# modem-v1-rev1.net
KiCad netlist of a schematic drawn in EAGLE
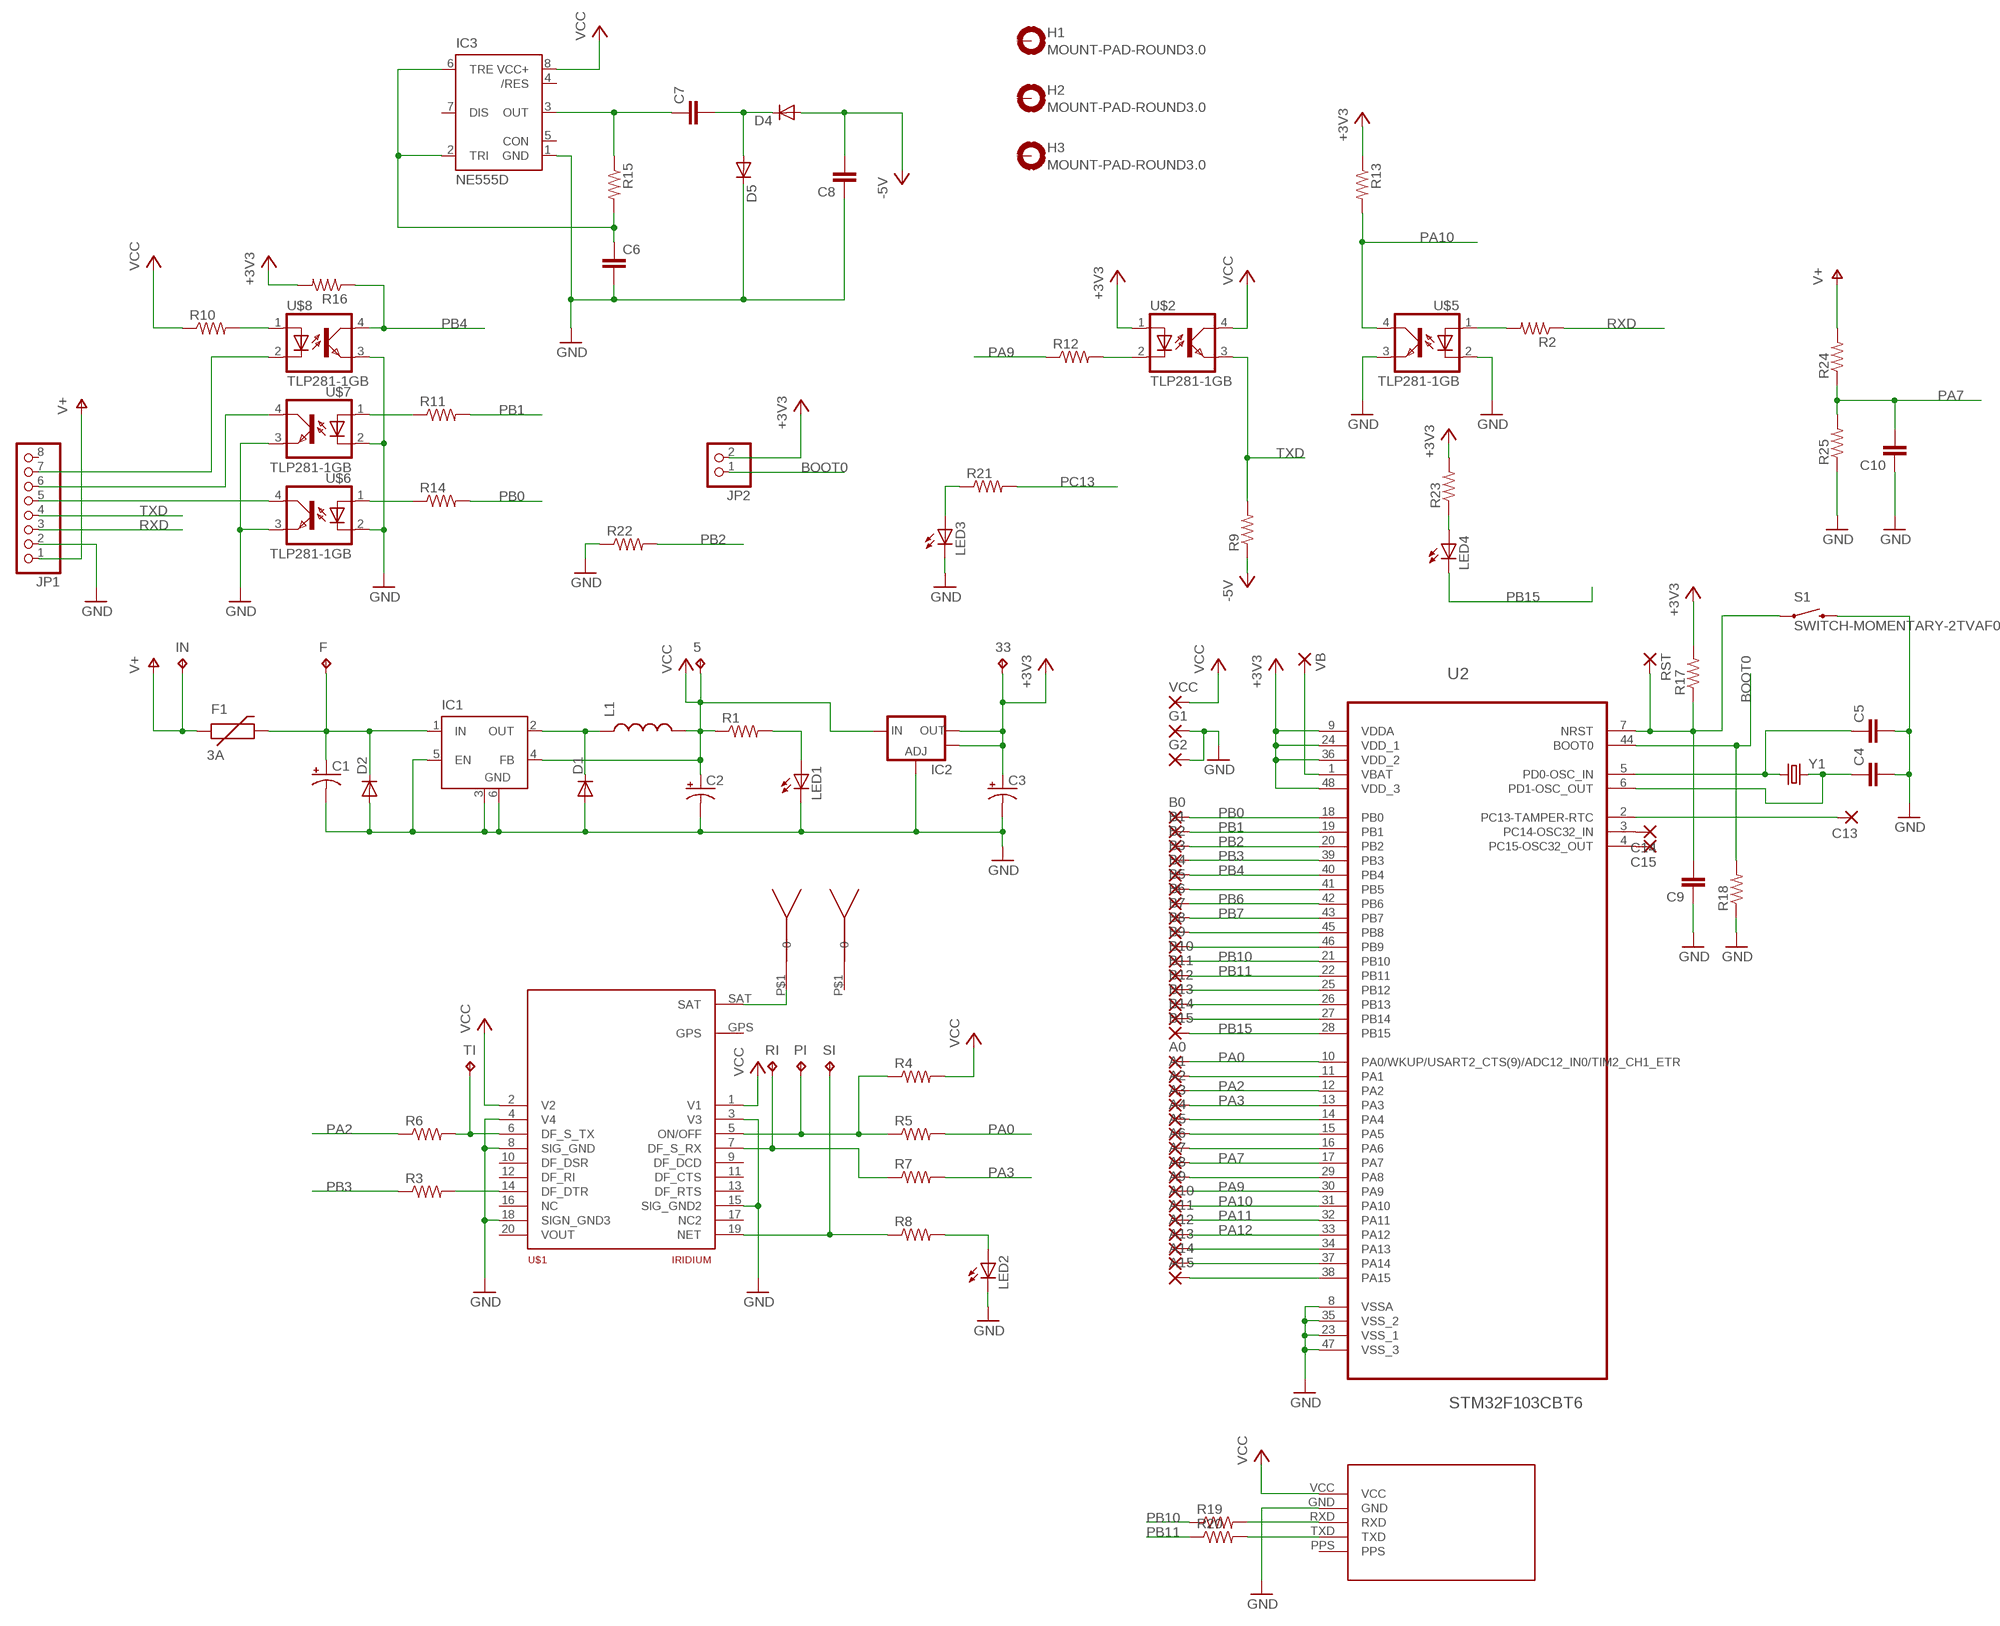
[diagram p0: schematic, sheet 1]

(export (version "E")
  (design (tool "Eeschema 10.0.6"))
  (components
    (comp (ref "5")
      (value "TPTP15R")
      (footprint "eagle-import:TP15R")
      (libsource (lib "eagle-import") (part "TPTP15R"))
    )
    (comp (ref "33")
      (value "TP1")
      (footprint "eagle-import:TP15R")
      (libsource (lib "eagle-import") (part "TPTP15R"))
    )
    (comp (ref "A0")
      (value "1,6/0,8")
      (footprint "eagle-import:1,6_0,8")
      (libsource (lib "eagle-import") (part "1,6/0,8"))
    )
    (comp (ref "A1")
      (value "1,6/0,8")
      (footprint "eagle-import:1,6_0,8")
      (libsource (lib "eagle-import") (part "1,6/0,8"))
    )
    (comp (ref "A2")
      (value "1,6/0,8")
      (footprint "eagle-import:1,6_0,8")
      (libsource (lib "eagle-import") (part "1,6/0,8"))
    )
    (comp (ref "A3")
      (value "1,6/0,8")
      (footprint "eagle-import:1,6_0,8")
      (libsource (lib "eagle-import") (part "1,6/0,8"))
    )
    (comp (ref "A4")
      (value "1,6/0,8")
      (footprint "eagle-import:1,6_0,8")
      (libsource (lib "eagle-import") (part "1,6/0,8"))
    )
    (comp (ref "A5")
      (value "1,6/0,8")
      (footprint "eagle-import:1,6_0,8")
      (libsource (lib "eagle-import") (part "1,6/0,8"))
    )
    (comp (ref "A6")
      (value "1,6/0,8")
      (footprint "eagle-import:1,6_0,8")
      (libsource (lib "eagle-import") (part "1,6/0,8"))
    )
    (comp (ref "A7")
      (value "1,6/0,8")
      (footprint "eagle-import:1,6_0,8")
      (libsource (lib "eagle-import") (part "1,6/0,8"))
    )
    (comp (ref "A8")
      (value "1,6/0,8")
      (footprint "eagle-import:1,6_0,8")
      (libsource (lib "eagle-import") (part "1,6/0,8"))
    )
    (comp (ref "A9")
      (value "1,6/0,8")
      (footprint "eagle-import:1,6_0,8")
      (libsource (lib "eagle-import") (part "1,6/0,8"))
    )
    (comp (ref "A10")
      (value "1,6/0,8")
      (footprint "eagle-import:1,6_0,8")
      (libsource (lib "eagle-import") (part "1,6/0,8"))
    )
    (comp (ref "A11")
      (value "1,6/0,8")
      (footprint "eagle-import:1,6_0,8")
      (libsource (lib "eagle-import") (part "1,6/0,8"))
    )
    (comp (ref "A12")
      (value "1,6/0,8")
      (footprint "eagle-import:1,6_0,8")
      (libsource (lib "eagle-import") (part "1,6/0,8"))
    )
    (comp (ref "A13")
      (value "1,6/0,8")
      (footprint "eagle-import:1,6_0,8")
      (libsource (lib "eagle-import") (part "1,6/0,8"))
    )
    (comp (ref "A14")
      (value "1,6/0,8")
      (footprint "eagle-import:1,6_0,8")
      (libsource (lib "eagle-import") (part "1,6/0,8"))
    )
    (comp (ref "A15")
      (value "1,6/0,8")
      (footprint "eagle-import:1,6_0,8")
      (libsource (lib "eagle-import") (part "1,6/0,8"))
    )
    (comp (ref "B0")
      (value "1,6/0,8")
      (footprint "eagle-import:1,6_0,8")
      (libsource (lib "eagle-import") (part "1,6/0,8"))
    )
    (comp (ref "B1")
      (value "1,6/0,8")
      (footprint "eagle-import:1,6_0,8")
      (libsource (lib "eagle-import") (part "1,6/0,8"))
    )
    (comp (ref "B2")
      (value "1,6/0,8")
      (footprint "eagle-import:1,6_0,8")
      (libsource (lib "eagle-import") (part "1,6/0,8"))
    )
    (comp (ref "B3")
      (value "1,6/0,8")
      (footprint "eagle-import:1,6_0,8")
      (libsource (lib "eagle-import") (part "1,6/0,8"))
    )
    (comp (ref "B4")
      (value "1,6/0,8")
      (footprint "eagle-import:1,6_0,8")
      (libsource (lib "eagle-import") (part "1,6/0,8"))
    )
    (comp (ref "B5")
      (value "1,6/0,8")
      (footprint "eagle-import:1,6_0,8")
      (libsource (lib "eagle-import") (part "1,6/0,8"))
    )
    (comp (ref "B6")
      (value "1,6/0,8")
      (footprint "eagle-import:1,6_0,8")
      (libsource (lib "eagle-import") (part "1,6/0,8"))
    )
    (comp (ref "B7")
      (value "1,6/0,8")
      (footprint "eagle-import:1,6_0,8")
      (libsource (lib "eagle-import") (part "1,6/0,8"))
    )
    (comp (ref "B8")
      (value "1,6/0,8")
      (footprint "eagle-import:1,6_0,8")
      (libsource (lib "eagle-import") (part "1,6/0,8"))
    )
    (comp (ref "B9")
      (value "1,6/0,8")
      (footprint "eagle-import:1,6_0,8")
      (libsource (lib "eagle-import") (part "1,6/0,8"))
    )
    (comp (ref "B10")
      (value "1,6/0,8")
      (footprint "eagle-import:1,6_0,8")
      (libsource (lib "eagle-import") (part "1,6/0,8"))
    )
    (comp (ref "B11")
      (value "1,6/0,8")
      (footprint "eagle-import:1,6_0,8")
      (libsource (lib "eagle-import") (part "1,6/0,8"))
    )
    (comp (ref "B12")
      (value "1,6/0,8")
      (footprint "eagle-import:1,6_0,8")
      (libsource (lib "eagle-import") (part "1,6/0,8"))
    )
    (comp (ref "B13")
      (value "1,6/0,8")
      (footprint "eagle-import:1,6_0,8")
      (libsource (lib "eagle-import") (part "1,6/0,8"))
    )
    (comp (ref "B14")
      (value "1,6/0,8")
      (footprint "eagle-import:1,6_0,8")
      (libsource (lib "eagle-import") (part "1,6/0,8"))
    )
    (comp (ref "B15")
      (value "1,6/0,8")
      (footprint "eagle-import:1,6_0,8")
      (libsource (lib "eagle-import") (part "1,6/0,8"))
    )
    (comp (ref "C1")
      (value "CAP_POLG")
      (footprint "eagle-import:PANASONIC_G")
      (libsource (lib "eagle-import") (part "CAP_POLG"))
    )
    (comp (ref "C2")
      (value "CAP_POLD")
      (footprint "eagle-import:PANASONIC_D")
      (libsource (lib "eagle-import") (part "CAP_POLD"))
    )
    (comp (ref "C3")
      (value "CAP_POLD")
      (footprint "eagle-import:PANASONIC_D")
      (libsource (lib "eagle-import") (part "CAP_POLD"))
    )
    (comp (ref "C4")
      (value "CAP0805")
      (footprint "eagle-import:0805")
      (libsource (lib "eagle-import") (part "CAP0805"))
    )
    (comp (ref "C5")
      (value "CAP0805")
      (footprint "eagle-import:0805")
      (libsource (lib "eagle-import") (part "CAP0805"))
    )
    (comp (ref "C6")
      (value "CAP0805")
      (footprint "eagle-import:0805")
      (libsource (lib "eagle-import") (part "CAP0805"))
    )
    (comp (ref "C7")
      (value "CAP0805")
      (footprint "eagle-import:0805")
      (libsource (lib "eagle-import") (part "CAP0805"))
    )
    (comp (ref "C8")
      (value "CAP0805")
      (footprint "eagle-import:0805")
      (libsource (lib "eagle-import") (part "CAP0805"))
    )
    (comp (ref "C9")
      (value "CAP0805")
      (footprint "eagle-import:0805")
      (libsource (lib "eagle-import") (part "CAP0805"))
    )
    (comp (ref "C10")
      (value "CAP0805")
      (footprint "eagle-import:0805")
      (libsource (lib "eagle-import") (part "CAP0805"))
    )
    (comp (ref "C13")
      (value "1,6/0,8")
      (footprint "eagle-import:1,6_0,8")
      (libsource (lib "eagle-import") (part "1,6/0,8"))
    )
    (comp (ref "C14")
      (value "1,6/0,8")
      (footprint "eagle-import:1,6_0,8")
      (libsource (lib "eagle-import") (part "1,6/0,8"))
    )
    (comp (ref "C15")
      (value "1,6/0,8")
      (footprint "eagle-import:1,6_0,8")
      (libsource (lib "eagle-import") (part "1,6/0,8"))
    )
    (comp (ref "D1")
      (value "DIODESMA-KIT")
      (footprint "eagle-import:SMA-DIODE-KIT")
      (libsource (lib "eagle-import") (part "DIODESMA-KIT"))
    )
    (comp (ref "D2")
      (value "DIODESMB")
      (footprint "eagle-import:SMB-DIODE")
      (libsource (lib "eagle-import") (part "DIODESMB"))
    )
    (comp (ref "D4")
      (value "DIODESOD")
      (footprint "eagle-import:SOD-323")
      (libsource (lib "eagle-import") (part "DIODESOD"))
    )
    (comp (ref "D5")
      (value "DIODESOD")
      (footprint "eagle-import:SOD-323")
      (libsource (lib "eagle-import") (part "DIODESOD"))
    )
    (comp (ref "F")
      (value "TPTP15R")
      (footprint "eagle-import:TP15R")
      (libsource (lib "eagle-import") (part "TPTP15R"))
    )
    (comp (ref "F1")
      (value "3A")
      (footprint "eagle-import:PTC")
      (libsource (lib "eagle-import") (part "PTCPTH"))
    )
    (comp (ref "G1")
      (value "1,6/0,8")
      (footprint "eagle-import:1,6_0,8")
      (libsource (lib "eagle-import") (part "1,6/0,8"))
    )
    (comp (ref "G2")
      (value "1,6/0,8")
      (footprint "eagle-import:1,6_0,8")
      (libsource (lib "eagle-import") (part "1,6/0,8"))
    )
    (comp (ref "H1")
      (value "MOUNT-PAD-ROUND3.0")
      (footprint "eagle-import:3,0-PAD")
      (libsource (lib "eagle-import") (part "MOUNT-PAD-ROUND3.0"))
    )
    (comp (ref "H2")
      (value "MOUNT-PAD-ROUND3.0")
      (footprint "eagle-import:3,0-PAD")
      (libsource (lib "eagle-import") (part "MOUNT-PAD-ROUND3.0"))
    )
    (comp (ref "H3")
      (value "MOUNT-PAD-ROUND3.0")
      (footprint "eagle-import:3,0-PAD")
      (libsource (lib "eagle-import") (part "MOUNT-PAD-ROUND3.0"))
    )
    (comp (ref "IC1")
      (value "LM2596S")
      (footprint "eagle-import:TO263-5")
      (libsource (lib "eagle-import") (part "LM2596S"))
    )
    (comp (ref "IC2")
      (value "V_REG_LM1117SOT223")
      (footprint "eagle-import:SOT223")
      (libsource (lib "eagle-import") (part "V_REG_LM1117SOT223"))
    )
    (comp (ref "IC3")
      (value "NE555D")
      (footprint "eagle-import:SO08")
      (libsource (lib "eagle-import") (part "NE555D"))
    )
    (comp (ref "IN")
      (value "IN")
      (footprint "eagle-import:TP15R")
      (libsource (lib "eagle-import") (part "TPTP15R"))
    )
    (comp (ref "JP1")
      (value "PINHD-1X8")
      (footprint "eagle-import:1X08")
      (libsource (lib "eagle-import") (part "PINHD-1X8"))
    )
    (comp (ref "JP2")
      (value "PINHD-1X2")
      (footprint "eagle-import:1X02")
      (libsource (lib "eagle-import") (part "PINHD-1X2"))
    )
    (comp (ref "L1")
      (value "INDUCTORPWR")
      (footprint "eagle-import:CDRH125")
      (libsource (lib "eagle-import") (part "INDUCTORPWR"))
    )
    (comp (ref "LED1")
      (value "LED-FKIT-1206")
      (footprint "eagle-import:FKIT-LED-1206")
      (libsource (lib "eagle-import") (part "LED-FKIT-1206"))
    )
    (comp (ref "LED2")
      (value "LED-FKIT-1206")
      (footprint "eagle-import:FKIT-LED-1206")
      (libsource (lib "eagle-import") (part "LED-FKIT-1206"))
    )
    (comp (ref "LED3")
      (value "LED-FKIT-1206")
      (footprint "eagle-import:FKIT-LED-1206")
      (libsource (lib "eagle-import") (part "LED-FKIT-1206"))
    )
    (comp (ref "LED4")
      (value "LED-FKIT-1206")
      (footprint "eagle-import:FKIT-LED-1206")
      (libsource (lib "eagle-import") (part "LED-FKIT-1206"))
    )
    (comp (ref "PI")
      (value "TPTP15R")
      (footprint "eagle-import:TP15R")
      (libsource (lib "eagle-import") (part "TPTP15R"))
    )
    (comp (ref "R1")
      (value "RESISTOR0805-RES")
      (footprint "eagle-import:0805")
      (libsource (lib "eagle-import") (part "RESISTOR0805-RES"))
    )
    (comp (ref "R2")
      (value "RESISTOR0805-RES")
      (footprint "eagle-import:0805")
      (libsource (lib "eagle-import") (part "RESISTOR0805-RES"))
    )
    (comp (ref "R3")
      (value "RESISTOR0805-RES")
      (footprint "eagle-import:0805")
      (libsource (lib "eagle-import") (part "RESISTOR0805-RES"))
    )
    (comp (ref "R4")
      (value "RESISTOR0805-RES")
      (footprint "eagle-import:0805")
      (libsource (lib "eagle-import") (part "RESISTOR0805-RES"))
    )
    (comp (ref "R5")
      (value "RESISTOR0805-RES")
      (footprint "eagle-import:0805")
      (libsource (lib "eagle-import") (part "RESISTOR0805-RES"))
    )
    (comp (ref "R6")
      (value "RESISTOR0805-RES")
      (footprint "eagle-import:0805")
      (libsource (lib "eagle-import") (part "RESISTOR0805-RES"))
    )
    (comp (ref "R7")
      (value "RESISTOR0805-RES")
      (footprint "eagle-import:0805")
      (libsource (lib "eagle-import") (part "RESISTOR0805-RES"))
    )
    (comp (ref "R8")
      (value "RESISTOR0805-RES")
      (footprint "eagle-import:0805")
      (libsource (lib "eagle-import") (part "RESISTOR0805-RES"))
    )
    (comp (ref "R9")
      (value "RESISTOR0805-RES")
      (footprint "eagle-import:0805")
      (libsource (lib "eagle-import") (part "RESISTOR0805-RES"))
    )
    (comp (ref "R10")
      (value "RESISTOR0805-RES")
      (footprint "eagle-import:0805")
      (libsource (lib "eagle-import") (part "RESISTOR0805-RES"))
    )
    (comp (ref "R11")
      (value "RESISTOR0805-RES")
      (footprint "eagle-import:0805")
      (libsource (lib "eagle-import") (part "RESISTOR0805-RES"))
    )
    (comp (ref "R12")
      (value "RESISTOR0805-RES")
      (footprint "eagle-import:0805")
      (libsource (lib "eagle-import") (part "RESISTOR0805-RES"))
    )
    (comp (ref "R13")
      (value "RESISTOR0805-RES")
      (footprint "eagle-import:0805")
      (libsource (lib "eagle-import") (part "RESISTOR0805-RES"))
    )
    (comp (ref "R14")
      (value "RESISTOR0805-RES")
      (footprint "eagle-import:0805")
      (libsource (lib "eagle-import") (part "RESISTOR0805-RES"))
    )
    (comp (ref "R15")
      (value "RESISTOR0805-RES")
      (footprint "eagle-import:0805")
      (libsource (lib "eagle-import") (part "RESISTOR0805-RES"))
    )
    (comp (ref "R16")
      (value "RESISTOR0805-RES")
      (footprint "eagle-import:0805")
      (libsource (lib "eagle-import") (part "RESISTOR0805-RES"))
    )
    (comp (ref "R17")
      (value "RESISTOR0805-RES")
      (footprint "eagle-import:0805")
      (libsource (lib "eagle-import") (part "RESISTOR0805-RES"))
    )
    (comp (ref "R18")
      (value "RESISTOR0805-RES")
      (footprint "eagle-import:0805")
      (libsource (lib "eagle-import") (part "RESISTOR0805-RES"))
    )
    (comp (ref "R19")
      (value "RESISTOR0805-RES")
      (footprint "eagle-import:0805")
      (libsource (lib "eagle-import") (part "RESISTOR0805-RES"))
    )
    (comp (ref "R20")
      (value "RESISTOR0805-RES")
      (footprint "eagle-import:0805")
      (libsource (lib "eagle-import") (part "RESISTOR0805-RES"))
    )
    (comp (ref "R21")
      (value "RESISTOR0805-RES")
      (footprint "eagle-import:0805")
      (libsource (lib "eagle-import") (part "RESISTOR0805-RES"))
    )
    (comp (ref "R22")
      (value "RESISTOR0805-RES")
      (footprint "eagle-import:0805")
      (libsource (lib "eagle-import") (part "RESISTOR0805-RES"))
    )
    (comp (ref "R23")
      (value "RESISTOR0805-RES")
      (footprint "eagle-import:0805")
      (libsource (lib "eagle-import") (part "RESISTOR0805-RES"))
    )
    (comp (ref "R24")
      (value "RESISTOR0805-RES")
      (footprint "eagle-import:0805")
      (libsource (lib "eagle-import") (part "RESISTOR0805-RES"))
    )
    (comp (ref "R25")
      (value "RESISTOR0805-RES")
      (footprint "eagle-import:0805")
      (libsource (lib "eagle-import") (part "RESISTOR0805-RES"))
    )
    (comp (ref "RI")
      (value "TPTP15R")
      (footprint "eagle-import:TP15R")
      (libsource (lib "eagle-import") (part "TPTP15R"))
    )
    (comp (ref "RST")
      (value "1,6/0,8")
      (footprint "eagle-import:1,6_0,8")
      (libsource (lib "eagle-import") (part "1,6/0,8"))
    )
    (comp (ref "S1")
      (value "SWITCH-MOMENTARY-2TVAF02")
      (footprint "eagle-import:TVAF02")
      (libsource (lib "eagle-import") (part "SWITCH-MOMENTARY-2TVAF02"))
    )
    (comp (ref "SI")
      (value "TPTP15R")
      (footprint "eagle-import:TP15R")
      (libsource (lib "eagle-import") (part "TPTP15R"))
    )
    (comp (ref "TI")
      (value "TPTP15R")
      (footprint "eagle-import:TP15R")
      (libsource (lib "eagle-import") (part "TPTP15R"))
    )
    (comp (ref "U$1")
      (value "IRIDIUM-9602")
      (footprint "eagle-import:IRIDIUM-9602")
      (libsource (lib "eagle-import") (part "IRIDIUM-9602"))
    )
    (comp (ref "U$2")
      (value "TLP281-1GB")
      (footprint "eagle-import:TLP281")
      (libsource (lib "eagle-import") (part "TLP281-1GB"))
    )
    (comp (ref "U$3")
      (value "TAOGLASS-ANTENNA")
      (footprint "eagle-import:TAOGLASS-1")
      (libsource (lib "eagle-import") (part "TAOGLASS-ANTENNA"))
    )
    (comp (ref "U$4")
      (value "TAOGLASS-ANTENNA")
      (footprint "eagle-import:TAOGLASS-1")
      (libsource (lib "eagle-import") (part "TAOGLASS-ANTENNA"))
    )
    (comp (ref "U$5")
      (value "TLP281-1GB")
      (footprint "eagle-import:TLP281")
      (libsource (lib "eagle-import") (part "TLP281-1GB"))
    )
    (comp (ref "U$6")
      (value "TLP281-1GB")
      (footprint "eagle-import:TLP281")
      (libsource (lib "eagle-import") (part "TLP281-1GB"))
    )
    (comp (ref "U$7")
      (value "TLP281-1GB")
      (footprint "eagle-import:TLP281")
      (libsource (lib "eagle-import") (part "TLP281-1GB"))
    )
    (comp (ref "U$8")
      (value "TLP281-1GB")
      (footprint "eagle-import:TLP281")
      (libsource (lib "eagle-import") (part "TLP281-1GB"))
    )
    (comp (ref "U1")
      (value "UBLOX_NEO_6M")
      (footprint "eagle-import:NEO-6M")
      (libsource (lib "eagle-import") (part "UBLOX_NEO_6M"))
    )
    (comp (ref "U2")
      (value "STM32F103CBT6")
      (footprint "eagle-import:QFP50P900X900X160-48N")
      (libsource (lib "eagle-import") (part "STM32F103CBT6"))
    )
    (comp (ref "VB")
      (value "1,6/0,8")
      (footprint "eagle-import:1,6_0,8")
      (libsource (lib "eagle-import") (part "1,6/0,8"))
    )
    (comp (ref "VCC")
      (value "1,6/0,8")
      (footprint "eagle-import:1,6_0,8")
      (libsource (lib "eagle-import") (part "1,6/0,8"))
    )
    (comp (ref "Y1")
      (value "CRYSTAL10.5X4.8")
      (footprint "eagle-import:CRYSTAL-SMD-10.5X4.8-2PIN")
      (libsource (lib "eagle-import") (part "CRYSTAL10.5X4.8"))
    )
  )
  (nets
    (net (code "1") (name "+3V3") (class "Default")
      (node (ref "33") (pin "TP") (pinfunction "TP_TP") (pintype "input"))
      (node (ref "C3") (pin "+") (pinfunction "+_+") (pintype "passive"))
      (node (ref "IC2") (pin "2") (pinfunction "OUT_2") (pintype "output"))
      (node (ref "IC2") (pin "4") (pinfunction "OUT_4") (pintype "output"))
      (node (ref "JP2") (pin "2") (pinfunction "2_2") (pintype "passive"))
      (node (ref "R13") (pin "1") (pinfunction "1_1") (pintype "passive"))
      (node (ref "R16") (pin "2") (pinfunction "2_2") (pintype "passive"))
      (node (ref "R17") (pin "2") (pinfunction "2_2") (pintype "passive"))
      (node (ref "R23") (pin "2") (pinfunction "2_2") (pintype "passive"))
      (node (ref "U$2") (pin "1") (pinfunction "A_1") (pintype "passive"))
      (node (ref "U2") (pin "24") (pinfunction "VDD_1_24") (pintype "bidirectional"))
      (node (ref "U2") (pin "36") (pinfunction "VDD_2_36") (pintype "power_in"))
      (node (ref "U2") (pin "48") (pinfunction "VDD_3_48") (pintype "power_in"))
      (node (ref "U2") (pin "9") (pinfunction "VDDA_9") (pintype "power_in"))
    )
    (net (code "2") (name "-5V") (class "Default")
      (node (ref "C8") (pin "2") (pinfunction "2_2") (pintype "passive"))
      (node (ref "D4") (pin "2") (pinfunction "A_2") (pintype "passive"))
      (node (ref "R9") (pin "1") (pinfunction "1_1") (pintype "passive"))
    )
    (net (code "3") (name "/BOOT0") (class "Default")
      (node (ref "JP2") (pin "1") (pinfunction "1_1") (pintype "passive"))
      (node (ref "R18") (pin "2") (pinfunction "2_2") (pintype "passive"))
      (node (ref "U2") (pin "44") (pinfunction "BOOT0_44") (pintype "bidirectional"))
    )
    (net (code "4") (name "/PA0") (class "Default")
      (node (ref "A0") (pin "1") (pinfunction "P_1") (pintype "passive"))
      (node (ref "R5") (pin "2") (pinfunction "2_2") (pintype "passive"))
      (node (ref "U2") (pin "10") (pinfunction "PA0/WKUP/USART2_CTS(9)/ADC12_IN0/TIM2_CH1_ETR_10") (pintype "bidirectional"))
    )
    (net (code "5") (name "/PA2") (class "Default")
      (node (ref "A2") (pin "1") (pinfunction "P_1") (pintype "passive"))
      (node (ref "R6") (pin "1") (pinfunction "1_1") (pintype "passive"))
      (node (ref "U2") (pin "12") (pinfunction "PA2_12") (pintype "bidirectional"))
    )
    (net (code "6") (name "/PA3") (class "Default")
      (node (ref "A3") (pin "1") (pinfunction "P_1") (pintype "passive"))
      (node (ref "R7") (pin "2") (pinfunction "2_2") (pintype "passive"))
      (node (ref "U2") (pin "13") (pinfunction "PA3_13") (pintype "bidirectional"))
    )
    (net (code "7") (name "/PA7") (class "Default")
      (node (ref "A7") (pin "1") (pinfunction "P_1") (pintype "passive"))
      (node (ref "C10") (pin "2") (pinfunction "2_2") (pintype "passive"))
      (node (ref "R24") (pin "1") (pinfunction "1_1") (pintype "passive"))
      (node (ref "R25") (pin "2") (pinfunction "2_2") (pintype "passive"))
      (node (ref "U2") (pin "17") (pinfunction "PA7_17") (pintype "bidirectional"))
    )
    (net (code "8") (name "/PA9") (class "Default")
      (node (ref "A9") (pin "1") (pinfunction "P_1") (pintype "passive"))
      (node (ref "R12") (pin "1") (pinfunction "1_1") (pintype "passive"))
      (node (ref "U2") (pin "30") (pinfunction "PA9_30") (pintype "bidirectional"))
    )
    (net (code "9") (name "/PA10") (class "Default")
      (node (ref "A10") (pin "1") (pinfunction "P_1") (pintype "passive"))
      (node (ref "R13") (pin "2") (pinfunction "2_2") (pintype "passive"))
      (node (ref "U$5") (pin "4") (pinfunction "COL_4") (pintype "passive"))
      (node (ref "U2") (pin "31") (pinfunction "PA10_31") (pintype "bidirectional"))
    )
    (net (code "10") (name "/PA11") (class "Default")
      (node (ref "A11") (pin "1") (pinfunction "P_1") (pintype "passive"))
      (node (ref "U2") (pin "32") (pinfunction "PA11_32") (pintype "power_in"))
    )
    (net (code "11") (name "/PA12") (class "Default")
      (node (ref "A12") (pin "1") (pinfunction "P_1") (pintype "passive"))
      (node (ref "U2") (pin "33") (pinfunction "PA12_33") (pintype "bidirectional"))
    )
    (net (code "12") (name "/PB0") (class "Default")
      (node (ref "B0") (pin "1") (pinfunction "P_1") (pintype "passive"))
      (node (ref "R14") (pin "2") (pinfunction "2_2") (pintype "passive"))
      (node (ref "U2") (pin "18") (pinfunction "PB0_18") (pintype "bidirectional"))
    )
    (net (code "13") (name "/PB1") (class "Default")
      (node (ref "B1") (pin "1") (pinfunction "P_1") (pintype "passive"))
      (node (ref "R11") (pin "2") (pinfunction "2_2") (pintype "passive"))
      (node (ref "U2") (pin "19") (pinfunction "PB1_19") (pintype "bidirectional"))
    )
    (net (code "14") (name "/PB2") (class "Default")
      (node (ref "B2") (pin "1") (pinfunction "P_1") (pintype "passive"))
      (node (ref "R22") (pin "2") (pinfunction "2_2") (pintype "passive"))
      (node (ref "U2") (pin "20") (pinfunction "PB2_20") (pintype "bidirectional"))
    )
    (net (code "15") (name "/PB3") (class "Default")
      (node (ref "B3") (pin "1") (pinfunction "P_1") (pintype "passive"))
      (node (ref "R3") (pin "1") (pinfunction "1_1") (pintype "passive"))
      (node (ref "U2") (pin "39") (pinfunction "PB3_39") (pintype "bidirectional"))
    )
    (net (code "16") (name "/PB4") (class "Default")
      (node (ref "B4") (pin "1") (pinfunction "P_1") (pintype "passive"))
      (node (ref "R16") (pin "1") (pinfunction "1_1") (pintype "passive"))
      (node (ref "U$8") (pin "4") (pinfunction "COL_4") (pintype "passive"))
      (node (ref "U2") (pin "40") (pinfunction "PB4_40") (pintype "bidirectional"))
    )
    (net (code "17") (name "/PB6") (class "Default")
      (node (ref "B6") (pin "1") (pinfunction "P_1") (pintype "passive"))
      (node (ref "U2") (pin "42") (pinfunction "PB6_42") (pintype "bidirectional"))
    )
    (net (code "18") (name "/PB7") (class "Default")
      (node (ref "B7") (pin "1") (pinfunction "P_1") (pintype "passive"))
      (node (ref "U2") (pin "43") (pinfunction "PB7_43") (pintype "bidirectional"))
    )
    (net (code "19") (name "/PB10") (class "Default")
      (node (ref "B10") (pin "1") (pinfunction "P_1") (pintype "passive"))
      (node (ref "R19") (pin "1") (pinfunction "1_1") (pintype "passive"))
      (node (ref "U2") (pin "21") (pinfunction "PB10_21") (pintype "bidirectional"))
    )
    (net (code "20") (name "/PB11") (class "Default")
      (node (ref "B11") (pin "1") (pinfunction "P_1") (pintype "passive"))
      (node (ref "R20") (pin "1") (pinfunction "1_1") (pintype "passive"))
      (node (ref "U2") (pin "22") (pinfunction "PB11_22") (pintype "bidirectional"))
    )
    (net (code "21") (name "/PB15") (class "Default")
      (node (ref "B15") (pin "1") (pinfunction "P_1") (pintype "passive"))
      (node (ref "LED4") (pin "C") (pinfunction "C_C") (pintype "passive"))
      (node (ref "U2") (pin "28") (pinfunction "PB15_28") (pintype "bidirectional"))
    )
    (net (code "22") (name "/PC13") (class "Default")
      (node (ref "C13") (pin "1") (pinfunction "P_1") (pintype "passive"))
      (node (ref "R21") (pin "2") (pinfunction "2_2") (pintype "passive"))
      (node (ref "U2") (pin "2") (pinfunction "PC13-TAMPER-RTC_2") (pintype "bidirectional"))
    )
    (net (code "23") (name "/RXD") (class "Default")
      (node (ref "JP1") (pin "3") (pinfunction "3_3") (pintype "passive"))
      (node (ref "R2") (pin "1") (pinfunction "1_1") (pintype "passive"))
    )
    (net (code "24") (name "/TXD") (class "Default")
      (node (ref "JP1") (pin "4") (pinfunction "4_4") (pintype "passive"))
      (node (ref "R9") (pin "2") (pinfunction "2_2") (pintype "passive"))
      (node (ref "U$2") (pin "3") (pinfunction "EMIT_3") (pintype "passive"))
    )
    (net (code "25") (name "GND") (class "Default")
      (node (ref "C1") (pin "-") (pinfunction "-_-") (pintype "passive"))
      (node (ref "C10") (pin "1") (pinfunction "1_1") (pintype "passive"))
      (node (ref "C2") (pin "-") (pinfunction "-_-") (pintype "passive"))
      (node (ref "C3") (pin "-") (pinfunction "-_-") (pintype "passive"))
      (node (ref "C4") (pin "2") (pinfunction "2_2") (pintype "passive"))
      (node (ref "C5") (pin "2") (pinfunction "2_2") (pintype "passive"))
      (node (ref "C6") (pin "2") (pinfunction "2_2") (pintype "passive"))
      (node (ref "C8") (pin "1") (pinfunction "1_1") (pintype "passive"))
      (node (ref "C9") (pin "1") (pinfunction "1_1") (pintype "passive"))
      (node (ref "D1") (pin "A") (pinfunction "A_A") (pintype "passive"))
      (node (ref "D2") (pin "A") (pinfunction "A_A") (pintype "passive"))
      (node (ref "D5") (pin "1") (pinfunction "C_1") (pintype "passive"))
      (node (ref "G1") (pin "1") (pinfunction "P_1") (pintype "passive"))
      (node (ref "G2") (pin "1") (pinfunction "P_1") (pintype "passive"))
      (node (ref "IC1") (pin "3") (pinfunction "GND_3") (pintype "power_in"))
      (node (ref "IC1") (pin "5") (pinfunction "EN_5") (pintype "input"))
      (node (ref "IC1") (pin "6") (pinfunction "GND_6") (pintype "power_in"))
      (node (ref "IC2") (pin "1") (pinfunction "ADJ_1") (pintype "input"))
      (node (ref "IC3") (pin "1") (pinfunction "GND_1") (pintype "power_in"))
      (node (ref "JP1") (pin "2") (pinfunction "2_2") (pintype "passive"))
      (node (ref "LED1") (pin "C") (pinfunction "C_C") (pintype "passive"))
      (node (ref "LED2") (pin "C") (pinfunction "C_C") (pintype "passive"))
      (node (ref "LED3") (pin "C") (pinfunction "C_C") (pintype "passive"))
      (node (ref "R18") (pin "1") (pinfunction "1_1") (pintype "passive"))
      (node (ref "R22") (pin "1") (pinfunction "1_1") (pintype "passive"))
      (node (ref "R25") (pin "1") (pinfunction "1_1") (pintype "passive"))
      (node (ref "S1") (pin "1A") (pinfunction "2_1A") (pintype "passive"))
      (node (ref "U$1") (pin "15") (pinfunction "SIG_GND2_15") (pintype "bidirectional"))
      (node (ref "U$1") (pin "18") (pinfunction "SIGN_GND3_18") (pintype "bidirectional"))
      (node (ref "U$1") (pin "3") (pinfunction "V3_3") (pintype "bidirectional"))
      (node (ref "U$1") (pin "4") (pinfunction "V4_4") (pintype "bidirectional"))
      (node (ref "U$1") (pin "8") (pinfunction "SIG_GND_8") (pintype "bidirectional"))
      (node (ref "U$5") (pin "2") (pinfunction "C_2") (pintype "passive"))
      (node (ref "U$5") (pin "3") (pinfunction "EMIT_3") (pintype "passive"))
      (node (ref "U$6") (pin "2") (pinfunction "C_2") (pintype "passive"))
      (node (ref "U$6") (pin "3") (pinfunction "EMIT_3") (pintype "passive"))
      (node (ref "U$7") (pin "2") (pinfunction "C_2") (pintype "passive"))
      (node (ref "U$7") (pin "3") (pinfunction "EMIT_3") (pintype "passive"))
      (node (ref "U$8") (pin "3") (pinfunction "EMIT_3") (pintype "passive"))
      (node (ref "U1") (pin "GND") (pinfunction "GND_GND") (pintype "bidirectional"))
      (node (ref "U2") (pin "23") (pinfunction "VSS_1_23") (pintype "bidirectional"))
      (node (ref "U2") (pin "35") (pinfunction "VSS_2_35") (pintype "passive"))
      (node (ref "U2") (pin "47") (pinfunction "VSS_3_47") (pintype "passive"))
      (node (ref "U2") (pin "8") (pinfunction "VSSA_8") (pintype "passive"))
    )
    (net (code "26") (name "Net-(A1-P)") (class "Default")
      (node (ref "A1") (pin "1") (pinfunction "P_1") (pintype "passive"))
      (node (ref "U2") (pin "11") (pinfunction "PA1_11") (pintype "bidirectional"))
    )
    (net (code "27") (name "Net-(A4-P)") (class "Default")
      (node (ref "A4") (pin "1") (pinfunction "P_1") (pintype "passive"))
      (node (ref "U2") (pin "14") (pinfunction "PA4_14") (pintype "bidirectional"))
    )
    (net (code "28") (name "Net-(A5-P)") (class "Default")
      (node (ref "A5") (pin "1") (pinfunction "P_1") (pintype "passive"))
      (node (ref "U2") (pin "15") (pinfunction "PA5_15") (pintype "bidirectional"))
    )
    (net (code "29") (name "Net-(A6-P)") (class "Default")
      (node (ref "A6") (pin "1") (pinfunction "P_1") (pintype "passive"))
      (node (ref "U2") (pin "16") (pinfunction "PA6_16") (pintype "bidirectional"))
    )
    (net (code "30") (name "Net-(A8-P)") (class "Default")
      (node (ref "A8") (pin "1") (pinfunction "P_1") (pintype "passive"))
      (node (ref "U2") (pin "29") (pinfunction "PA8_29") (pintype "bidirectional"))
    )
    (net (code "31") (name "Net-(A13-P)") (class "Default")
      (node (ref "A13") (pin "1") (pinfunction "P_1") (pintype "passive"))
      (node (ref "U2") (pin "34") (pinfunction "PA13_34") (pintype "bidirectional"))
    )
    (net (code "32") (name "Net-(A14-P)") (class "Default")
      (node (ref "A14") (pin "1") (pinfunction "P_1") (pintype "passive"))
      (node (ref "U2") (pin "37") (pinfunction "PA14_37") (pintype "bidirectional"))
    )
    (net (code "33") (name "Net-(A15-P)") (class "Default")
      (node (ref "A15") (pin "1") (pinfunction "P_1") (pintype "passive"))
      (node (ref "U2") (pin "38") (pinfunction "PA15_38") (pintype "bidirectional"))
    )
    (net (code "34") (name "Net-(B5-P)") (class "Default")
      (node (ref "B5") (pin "1") (pinfunction "P_1") (pintype "passive"))
      (node (ref "U2") (pin "41") (pinfunction "PB5_41") (pintype "bidirectional"))
    )
    (net (code "35") (name "Net-(B8-P)") (class "Default")
      (node (ref "B8") (pin "1") (pinfunction "P_1") (pintype "passive"))
      (node (ref "U2") (pin "45") (pinfunction "PB8_45") (pintype "bidirectional"))
    )
    (net (code "36") (name "Net-(B9-P)") (class "Default")
      (node (ref "B9") (pin "1") (pinfunction "P_1") (pintype "passive"))
      (node (ref "U2") (pin "46") (pinfunction "PB9_46") (pintype "bidirectional"))
    )
    (net (code "37") (name "Net-(B12-P)") (class "Default")
      (node (ref "B12") (pin "1") (pinfunction "P_1") (pintype "passive"))
      (node (ref "U2") (pin "25") (pinfunction "PB12_25") (pintype "bidirectional"))
    )
    (net (code "38") (name "Net-(B13-P)") (class "Default")
      (node (ref "B13") (pin "1") (pinfunction "P_1") (pintype "passive"))
      (node (ref "U2") (pin "26") (pinfunction "PB13_26") (pintype "bidirectional"))
    )
    (net (code "39") (name "Net-(B14-P)") (class "Default")
      (node (ref "B14") (pin "1") (pinfunction "P_1") (pintype "passive"))
      (node (ref "U2") (pin "27") (pinfunction "PB14_27") (pintype "bidirectional"))
    )
    (net (code "40") (name "Net-(C14-P)") (class "Default")
      (node (ref "C14") (pin "1") (pinfunction "P_1") (pintype "passive"))
      (node (ref "U2") (pin "3") (pinfunction "PC14-OSC32_IN_3") (pintype "bidirectional"))
    )
    (net (code "41") (name "Net-(C15-P)") (class "Default")
      (node (ref "C15") (pin "1") (pinfunction "P_1") (pintype "passive"))
      (node (ref "U2") (pin "4") (pinfunction "PC15-OSC32_OUT_4") (pintype "bidirectional"))
    )
    (net (code "42") (name "Net-(D4-C)") (class "Default")
      (node (ref "C7") (pin "2") (pinfunction "2_2") (pintype "passive"))
      (node (ref "D4") (pin "1") (pinfunction "C_1") (pintype "passive"))
      (node (ref "D5") (pin "2") (pinfunction "A_2") (pintype "passive"))
    )
    (net (code "43") (name "Net-(F1-2)") (class "Default")
      (node (ref "C1") (pin "+") (pinfunction "+_+") (pintype "passive"))
      (node (ref "D2") (pin "C") (pinfunction "C_C") (pintype "passive"))
      (node (ref "F") (pin "TP") (pinfunction "TP_TP") (pintype "input"))
      (node (ref "F1") (pin "P$2") (pinfunction "2_P$2") (pintype "bidirectional"))
      (node (ref "IC1") (pin "1") (pinfunction "IN_1") (pintype "input"))
    )
    (net (code "44") (name "Net-(IC1-OUT)") (class "Default")
      (node (ref "D1") (pin "C") (pinfunction "C_C") (pintype "passive"))
      (node (ref "IC1") (pin "2") (pinfunction "OUT_2") (pintype "output"))
      (node (ref "L1") (pin "1") (pinfunction "1_1") (pintype "passive"))
    )
    (net (code "45") (name "Net-(IC3-OUT)") (class "Default")
      (node (ref "C7") (pin "1") (pinfunction "1_1") (pintype "passive"))
      (node (ref "IC3") (pin "3") (pinfunction "OUT_3") (pintype "output"))
      (node (ref "R15") (pin "1") (pinfunction "1_1") (pintype "passive"))
    )
    (net (code "46") (name "Net-(IC3-TRE)") (class "Default")
      (node (ref "C6") (pin "1") (pinfunction "1_1") (pintype "passive"))
      (node (ref "IC3") (pin "2") (pinfunction "TRI_2") (pintype "input"))
      (node (ref "IC3") (pin "6") (pinfunction "TRE_6") (pintype "input"))
      (node (ref "R15") (pin "2") (pinfunction "2_2") (pintype "passive"))
    )
    (net (code "47") (name "Net-(LED1-PadA)") (class "Default")
      (node (ref "LED1") (pin "A") (pinfunction "A_A") (pintype "passive"))
      (node (ref "R1") (pin "2") (pinfunction "2_2") (pintype "passive"))
    )
    (net (code "48") (name "Net-(LED2-PadA)") (class "Default")
      (node (ref "LED2") (pin "A") (pinfunction "A_A") (pintype "passive"))
      (node (ref "R8") (pin "2") (pinfunction "2_2") (pintype "passive"))
    )
    (net (code "49") (name "Net-(LED3-PadA)") (class "Default")
      (node (ref "LED3") (pin "A") (pinfunction "A_A") (pintype "passive"))
      (node (ref "R21") (pin "1") (pinfunction "1_1") (pintype "passive"))
    )
    (net (code "50") (name "Net-(LED4-PadA)") (class "Default")
      (node (ref "LED4") (pin "A") (pinfunction "A_A") (pintype "passive"))
      (node (ref "R23") (pin "1") (pinfunction "1_1") (pintype "passive"))
    )
    (net (code "51") (name "Net-(R19-Pad2)") (class "Default")
      (node (ref "R19") (pin "2") (pinfunction "2_2") (pintype "passive"))
      (node (ref "U1") (pin "RXD") (pinfunction "RXD_RXD") (pintype "bidirectional"))
    )
    (net (code "52") (name "Net-(R20-Pad2)") (class "Default")
      (node (ref "R20") (pin "2") (pinfunction "2_2") (pintype "passive"))
      (node (ref "U1") (pin "TXD") (pinfunction "TXD_TXD") (pintype "bidirectional"))
    )
    (net (code "53") (name "Net-(RST-P)") (class "Default")
      (node (ref "C9") (pin "2") (pinfunction "2_2") (pintype "passive"))
      (node (ref "R17") (pin "1") (pinfunction "1_1") (pintype "passive"))
      (node (ref "RST") (pin "1") (pinfunction "P_1") (pintype "passive"))
      (node (ref "S1") (pin "1B") (pinfunction "1_1B") (pintype "passive"))
      (node (ref "U2") (pin "7") (pinfunction "NRST_7") (pintype "bidirectional"))
    )
    (net (code "54") (name "Net-(U$1-DF_DTR)") (class "Default")
      (node (ref "R3") (pin "2") (pinfunction "2_2") (pintype "passive"))
      (node (ref "U$1") (pin "14") (pinfunction "DF_DTR_14") (pintype "bidirectional"))
    )
    (net (code "55") (name "Net-(U$1-DF_S_RX)") (class "Default")
      (node (ref "R7") (pin "1") (pinfunction "1_1") (pintype "passive"))
      (node (ref "RI") (pin "TP") (pinfunction "TP_TP") (pintype "input"))
      (node (ref "U$1") (pin "7") (pinfunction "DF_S_RX_7") (pintype "bidirectional"))
    )
    (net (code "56") (name "Net-(U$1-DF_S_TX)") (class "Default")
      (node (ref "R6") (pin "2") (pinfunction "2_2") (pintype "passive"))
      (node (ref "TI") (pin "TP") (pinfunction "TP_TP") (pintype "input"))
      (node (ref "U$1") (pin "6") (pinfunction "DF_S_TX_6") (pintype "bidirectional"))
    )
    (net (code "57") (name "Net-(U$1-NET)") (class "Default")
      (node (ref "R8") (pin "1") (pinfunction "1_1") (pintype "passive"))
      (node (ref "SI") (pin "TP") (pinfunction "TP_TP") (pintype "input"))
      (node (ref "U$1") (pin "19") (pinfunction "NET_19") (pintype "bidirectional"))
    )
    (net (code "58") (name "Net-(U$1-ON{slash}OFF)") (class "Default")
      (node (ref "PI") (pin "TP") (pinfunction "TP_TP") (pintype "input"))
      (node (ref "R4") (pin "1") (pinfunction "1_1") (pintype "passive"))
      (node (ref "R5") (pin "1") (pinfunction "1_1") (pintype "passive"))
      (node (ref "U$1") (pin "5") (pinfunction "ON/OFF_5") (pintype "bidirectional"))
    )
    (net (code "59") (name "Net-(U$2-C)") (class "Default")
      (node (ref "R12") (pin "2") (pinfunction "2_2") (pintype "passive"))
      (node (ref "U$2") (pin "2") (pinfunction "C_2") (pintype "passive"))
    )
    (net (code "60") (name "Net-(U$3-0)") (class "Default")
      (node (ref "U$1") (pin "SAT") (pinfunction "SAT_SAT") (pintype "bidirectional"))
      (node (ref "U$3") (pin "P$1") (pinfunction "0_P$1") (pintype "bidirectional"))
    )
    (net (code "61") (name "Net-(U$5-A)") (class "Default")
      (node (ref "R2") (pin "2") (pinfunction "2_2") (pintype "passive"))
      (node (ref "U$5") (pin "1") (pinfunction "A_1") (pintype "passive"))
    )
    (net (code "62") (name "Net-(U$6-A)") (class "Default")
      (node (ref "R14") (pin "1") (pinfunction "1_1") (pintype "passive"))
      (node (ref "U$6") (pin "1") (pinfunction "A_1") (pintype "passive"))
    )
    (net (code "63") (name "Net-(U$6-COL)") (class "Default")
      (node (ref "JP1") (pin "5") (pinfunction "5_5") (pintype "passive"))
      (node (ref "U$6") (pin "4") (pinfunction "COL_4") (pintype "passive"))
    )
    (net (code "64") (name "Net-(U$7-A)") (class "Default")
      (node (ref "R11") (pin "1") (pinfunction "1_1") (pintype "passive"))
      (node (ref "U$7") (pin "1") (pinfunction "A_1") (pintype "passive"))
    )
    (net (code "65") (name "Net-(U$7-COL)") (class "Default")
      (node (ref "JP1") (pin "6") (pinfunction "6_6") (pintype "passive"))
      (node (ref "U$7") (pin "4") (pinfunction "COL_4") (pintype "passive"))
    )
    (net (code "66") (name "Net-(U$8-A)") (class "Default")
      (node (ref "R10") (pin "2") (pinfunction "2_2") (pintype "passive"))
      (node (ref "U$8") (pin "1") (pinfunction "A_1") (pintype "passive"))
    )
    (net (code "67") (name "Net-(U$8-C)") (class "Default")
      (node (ref "JP1") (pin "7") (pinfunction "7_7") (pintype "passive"))
      (node (ref "U$8") (pin "2") (pinfunction "C_2") (pintype "passive"))
    )
    (net (code "68") (name "Net-(U2-PD0-OSC_IN)") (class "Default")
      (node (ref "C5") (pin "1") (pinfunction "1_1") (pintype "passive"))
      (node (ref "U2") (pin "5") (pinfunction "PD0-OSC_IN_5") (pintype "bidirectional"))
      (node (ref "Y1") (pin "P$1") (pinfunction "1_P$1") (pintype "passive"))
    )
    (net (code "69") (name "Net-(U2-PD1-OSC_OUT)") (class "Default")
      (node (ref "C4") (pin "1") (pinfunction "1_1") (pintype "passive"))
      (node (ref "U2") (pin "6") (pinfunction "PD1-OSC_OUT_6") (pintype "bidirectional"))
      (node (ref "Y1") (pin "P$2") (pinfunction "2_P$2") (pintype "passive"))
    )
    (net (code "70") (name "Net-(U2-VBAT)") (class "Default")
      (node (ref "U2") (pin "1") (pinfunction "VBAT_1") (pintype "input"))
      (node (ref "VB") (pin "1") (pinfunction "P_1") (pintype "passive"))
    )
    (net (code "71") (name "V+") (class "Default")
      (node (ref "F1") (pin "P$1") (pinfunction "1_P$1") (pintype "bidirectional"))
      (node (ref "IN") (pin "TP") (pinfunction "TP_TP") (pintype "input"))
      (node (ref "JP1") (pin "1") (pinfunction "1_1") (pintype "passive"))
      (node (ref "R24") (pin "2") (pinfunction "2_2") (pintype "passive"))
    )
    (net (code "72") (name "VCC") (class "Default")
      (node (ref "5") (pin "TP") (pinfunction "TP_TP") (pintype "input"))
      (node (ref "C2") (pin "+") (pinfunction "+_+") (pintype "passive"))
      (node (ref "IC1") (pin "4") (pinfunction "FB_4") (pintype "input"))
      (node (ref "IC2") (pin "3") (pinfunction "IN_3") (pintype "input"))
      (node (ref "IC3") (pin "8") (pinfunction "VCC+_8") (pintype "power_in"))
      (node (ref "L1") (pin "2") (pinfunction "2_2") (pintype "passive"))
      (node (ref "R1") (pin "1") (pinfunction "1_1") (pintype "passive"))
      (node (ref "R10") (pin "1") (pinfunction "1_1") (pintype "passive"))
      (node (ref "R4") (pin "2") (pinfunction "2_2") (pintype "passive"))
      (node (ref "U$1") (pin "1") (pinfunction "V1_1") (pintype "bidirectional"))
      (node (ref "U$1") (pin "2") (pinfunction "V2_2") (pintype "bidirectional"))
      (node (ref "U$2") (pin "4") (pinfunction "COL_4") (pintype "passive"))
      (node (ref "U1") (pin "VCC") (pinfunction "VCC_VCC") (pintype "bidirectional"))
      (node (ref "VCC") (pin "1") (pinfunction "P_1") (pintype "passive"))
    )
    (net (code "73") (name "unconnected-(H1-MOUNT-PadB3,0)") (class "Default")
      (node (ref "H1") (pin "B3,0") (pinfunction "MOUNT_B3,0") (pintype "passive"))
    )
    (net (code "74") (name "unconnected-(H2-MOUNT-PadB3,0)") (class "Default")
      (node (ref "H2") (pin "B3,0") (pinfunction "MOUNT_B3,0") (pintype "passive"))
    )
    (net (code "75") (name "unconnected-(H3-MOUNT-PadB3,0)") (class "Default")
      (node (ref "H3") (pin "B3,0") (pinfunction "MOUNT_B3,0") (pintype "passive"))
    )
    (net (code "76") (name "unconnected-(IC3-CON-Pad5)") (class "Default")
      (node (ref "IC3") (pin "5") (pinfunction "CON_5") (pintype "input"))
    )
    (net (code "77") (name "unconnected-(IC3-DIS-Pad7)") (class "Default")
      (node (ref "IC3") (pin "7") (pinfunction "DIS_7") (pintype "input"))
    )
    (net (code "78") (name "unconnected-(IC3-{slash}RES-Pad4)") (class "Default")
      (node (ref "IC3") (pin "4") (pinfunction "/RES_4") (pintype "input"))
    )
    (net (code "79") (name "unconnected-(JP1-Pad8)") (class "Default")
      (node (ref "JP1") (pin "8") (pinfunction "8_8") (pintype "passive"))
    )
    (net (code "80") (name "unconnected-(U$1-DF_CTS-Pad11)") (class "Default")
      (node (ref "U$1") (pin "11") (pinfunction "DF_CTS_11") (pintype "bidirectional"))
    )
    (net (code "81") (name "unconnected-(U$1-DF_DCD-Pad9)") (class "Default")
      (node (ref "U$1") (pin "9") (pinfunction "DF_DCD_9") (pintype "bidirectional"))
    )
    (net (code "82") (name "unconnected-(U$1-DF_DSR-Pad10)") (class "Default")
      (node (ref "U$1") (pin "10") (pinfunction "DF_DSR_10") (pintype "bidirectional"))
    )
    (net (code "83") (name "unconnected-(U$1-DF_RI-Pad12)") (class "Default")
      (node (ref "U$1") (pin "12") (pinfunction "DF_RI_12") (pintype "bidirectional"))
    )
    (net (code "84") (name "unconnected-(U$1-DF_RTS-Pad13)") (class "Default")
      (node (ref "U$1") (pin "13") (pinfunction "DF_RTS_13") (pintype "bidirectional"))
    )
    (net (code "85") (name "unconnected-(U$1-NC-Pad16)") (class "Default")
      (node (ref "U$1") (pin "16") (pinfunction "NC_16") (pintype "bidirectional"))
    )
    (net (code "86") (name "unconnected-(U$1-NC2-Pad17)") (class "Default")
      (node (ref "U$1") (pin "17") (pinfunction "NC2_17") (pintype "bidirectional"))
    )
    (net (code "87") (name "unconnected-(U$1-PadGPS)") (class "Default")
      (node (ref "U$1") (pin "GPS") (pinfunction "GPS_GPS") (pintype "bidirectional"))
    )
    (net (code "88") (name "unconnected-(U$1-VOUT-Pad20)") (class "Default")
      (node (ref "U$1") (pin "20") (pinfunction "VOUT_20") (pintype "bidirectional"))
    )
    (net (code "89") (name "unconnected-(U$4-0-PadP$1)") (class "Default")
      (node (ref "U$4") (pin "P$1") (pinfunction "0_P$1") (pintype "bidirectional"))
    )
    (net (code "90") (name "unconnected-(U1-PadPPS)") (class "Default")
      (node (ref "U1") (pin "PPS") (pinfunction "PPS_PPS") (pintype "bidirectional"))
    )
  )
)
